# RF-Test-1.net
KiCad netlist of a schematic drawn in EAGLE
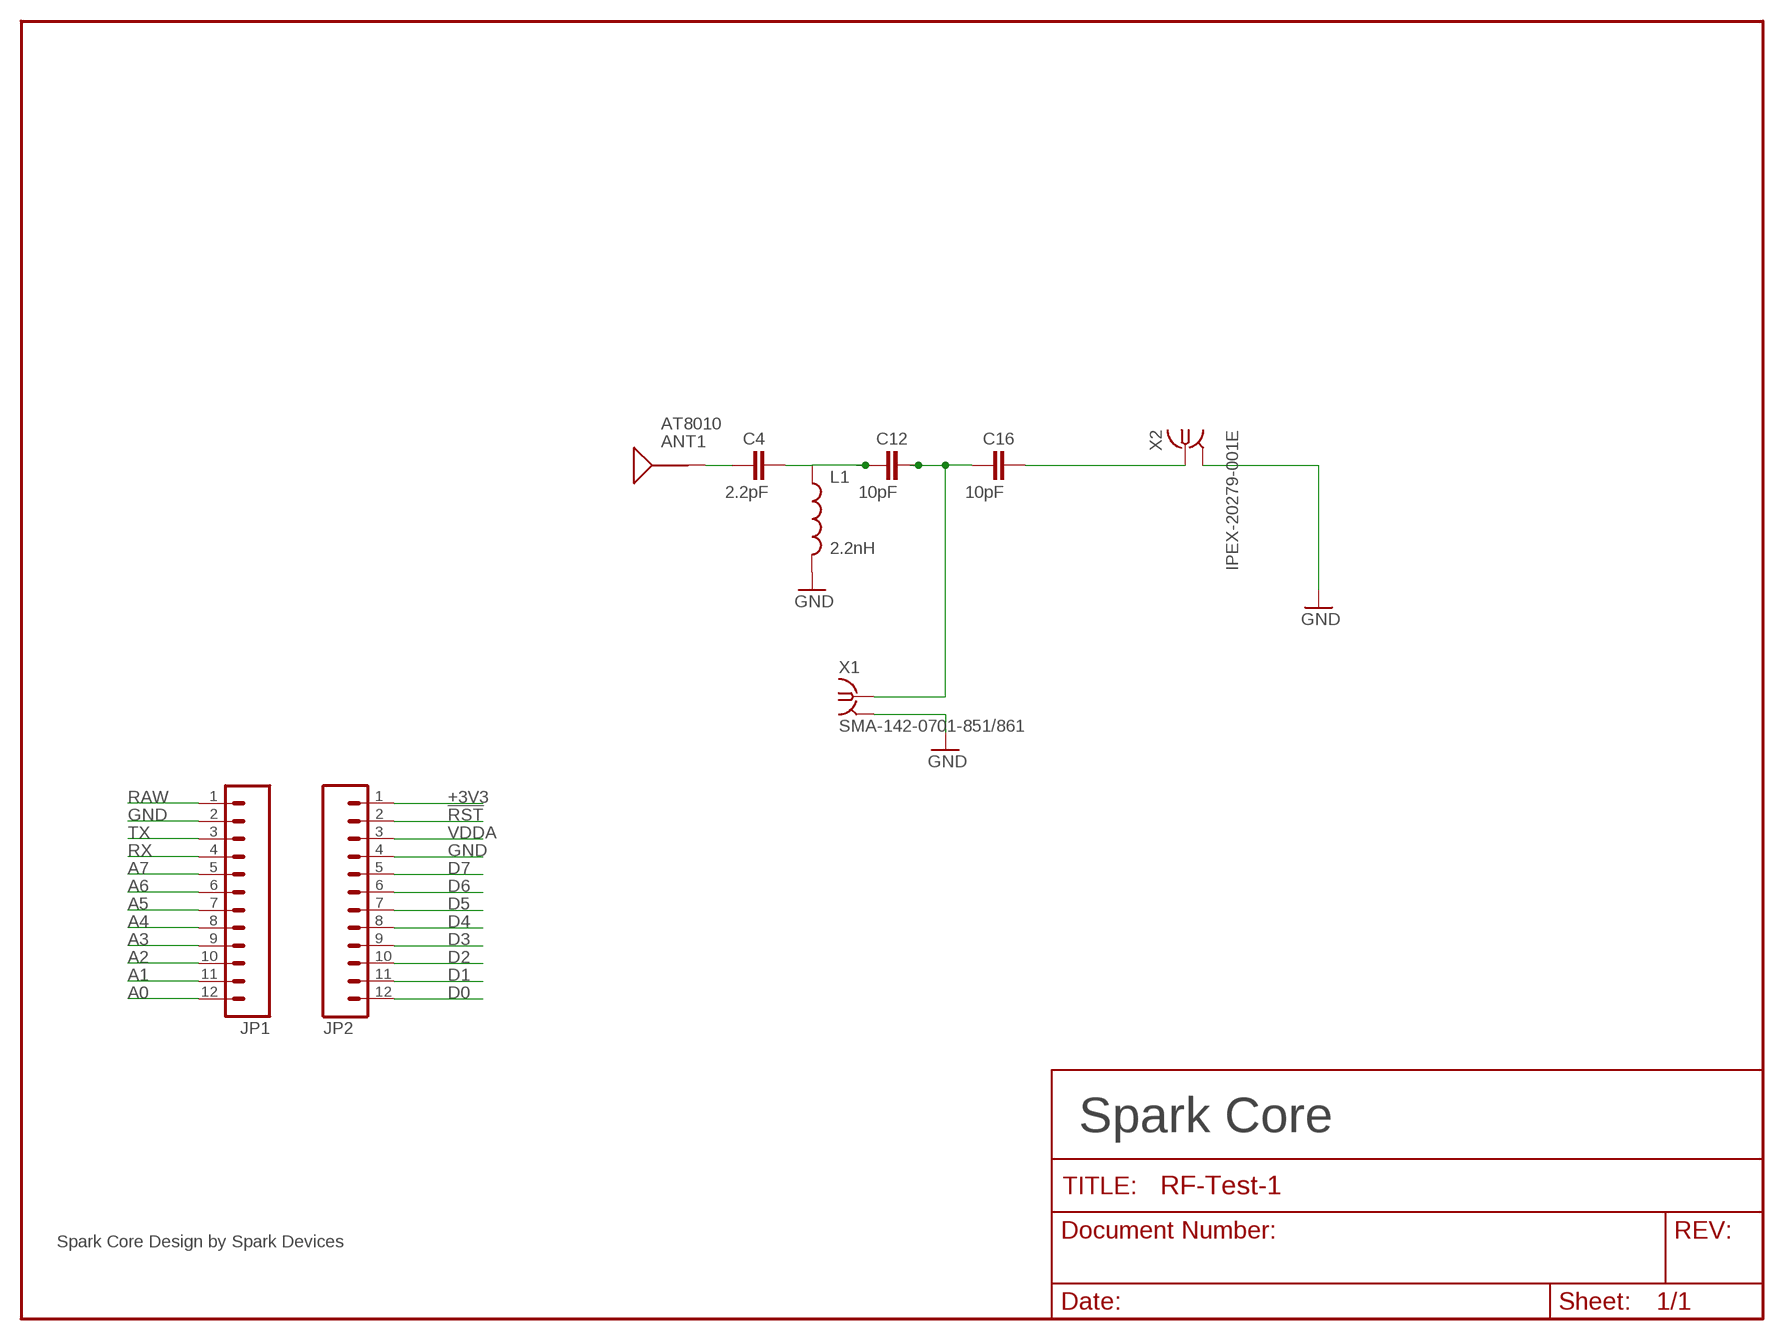
[diagram p0: schematic, sheet 1]

(export (version "E")
  (design (tool "Eeschema 10.0.6"))
  (components
    (comp (ref "ANT1")
      (value "AT8010")
      (footprint "eagle-import:AT8010")
      (libsource (lib "eagle-import") (part "AT8010"))
    )
    (comp (ref "C4")
      (value "2.2pF")
      (footprint "eagle-import:C0603")
      (libsource (lib "eagle-import") (part "C-EUC0603"))
    )
    (comp (ref "C12")
      (value "10pF")
      (footprint "eagle-import:C0603")
      (libsource (lib "eagle-import") (part "C-EUC0603"))
    )
    (comp (ref "C16")
      (value "10pF")
      (footprint "eagle-import:C0603")
      (libsource (lib "eagle-import") (part "C-EUC0603"))
    )
    (comp (ref "JP1")
      (value "M12PTH")
      (footprint "eagle-import:1X12")
      (libsource (lib "eagle-import") (part "M12PTH"))
    )
    (comp (ref "JP2")
      (value "M12PTH")
      (footprint "eagle-import:1X12")
      (libsource (lib "eagle-import") (part "M12PTH"))
    )
    (comp (ref "L1")
      (value "2.2nH")
      (footprint "eagle-import:0603")
      (libsource (lib "eagle-import") (part "INDUCTOR0603"))
    )
    (comp (ref "X1")
      (value "SMA-142-0701-851/861")
      (footprint "eagle-import:J502-ND-142-0701-851_861")
      (fields (field (name "MF") "JOHNSON COMPONENTS") (field (name "MPN") "142-0701-851"))
      (libsource (lib "eagle-import") (part "SMA-142-0701-851/861"))
    )
    (comp (ref "X2")
      (value "IPEX-20279-001E")
      (footprint "eagle-import:IPEX-20279-001E")
      (libsource (lib "eagle-import") (part "IPEX-20279-001E"))
    )
  )
  (nets
    (net (code "1") (name "/+3V3") (class "Default")
      (node (ref "JP2") (pin "1") (pinfunction "1_1") (pintype "passive"))
    )
    (net (code "2") (name "/A0") (class "Default")
      (node (ref "JP1") (pin "12") (pinfunction "12_12") (pintype "passive"))
    )
    (net (code "3") (name "/A1") (class "Default")
      (node (ref "JP1") (pin "11") (pinfunction "11_11") (pintype "passive"))
    )
    (net (code "4") (name "/A2") (class "Default")
      (node (ref "JP1") (pin "10") (pinfunction "10_10") (pintype "passive"))
    )
    (net (code "5") (name "/A3") (class "Default")
      (node (ref "JP1") (pin "9") (pinfunction "9_9") (pintype "passive"))
    )
    (net (code "6") (name "/A4") (class "Default")
      (node (ref "JP1") (pin "8") (pinfunction "8_8") (pintype "passive"))
    )
    (net (code "7") (name "/A5") (class "Default")
      (node (ref "JP1") (pin "7") (pinfunction "7_7") (pintype "passive"))
    )
    (net (code "8") (name "/A6") (class "Default")
      (node (ref "JP1") (pin "6") (pinfunction "6_6") (pintype "passive"))
    )
    (net (code "9") (name "/A7") (class "Default")
      (node (ref "JP1") (pin "5") (pinfunction "5_5") (pintype "passive"))
    )
    (net (code "10") (name "/D0") (class "Default")
      (node (ref "JP2") (pin "12") (pinfunction "12_12") (pintype "passive"))
    )
    (net (code "11") (name "/D1") (class "Default")
      (node (ref "JP2") (pin "11") (pinfunction "11_11") (pintype "passive"))
    )
    (net (code "12") (name "/D2") (class "Default")
      (node (ref "JP2") (pin "10") (pinfunction "10_10") (pintype "passive"))
    )
    (net (code "13") (name "/D3") (class "Default")
      (node (ref "JP2") (pin "9") (pinfunction "9_9") (pintype "passive"))
    )
    (net (code "14") (name "/D4") (class "Default")
      (node (ref "JP2") (pin "8") (pinfunction "8_8") (pintype "passive"))
    )
    (net (code "15") (name "/D5") (class "Default")
      (node (ref "JP2") (pin "7") (pinfunction "7_7") (pintype "passive"))
    )
    (net (code "16") (name "/D6") (class "Default")
      (node (ref "JP2") (pin "6") (pinfunction "6_6") (pintype "passive"))
    )
    (net (code "17") (name "/D7") (class "Default")
      (node (ref "JP2") (pin "5") (pinfunction "5_5") (pintype "passive"))
    )
    (net (code "18") (name "/RAW") (class "Default")
      (node (ref "JP1") (pin "1") (pinfunction "1_1") (pintype "passive"))
    )
    (net (code "19") (name "/RX") (class "Default")
      (node (ref "JP1") (pin "4") (pinfunction "4_4") (pintype "passive"))
    )
    (net (code "20") (name "/TX") (class "Default")
      (node (ref "JP1") (pin "3") (pinfunction "3_3") (pintype "passive"))
    )
    (net (code "21") (name "/VDDA") (class "Default")
      (node (ref "JP2") (pin "3") (pinfunction "3_3") (pintype "passive"))
    )
    (net (code "22") (name "/~{RST}") (class "Default")
      (node (ref "JP2") (pin "2") (pinfunction "2_2") (pintype "passive"))
    )
    (net (code "23") (name "GND") (class "Default")
      (node (ref "JP1") (pin "2") (pinfunction "2_2") (pintype "passive"))
      (node (ref "JP2") (pin "4") (pinfunction "4_4") (pintype "passive"))
      (node (ref "L1") (pin "2") (pinfunction "2_2") (pintype "passive"))
      (node (ref "X1") (pin "G@1") (pinfunction "2_G@1") (pintype "passive"))
      (node (ref "X1") (pin "G@2") (pinfunction "2_G@2") (pintype "passive"))
      (node (ref "X1") (pin "G@3") (pinfunction "2_G@3") (pintype "passive"))
      (node (ref "X1") (pin "G@4") (pinfunction "2_G@4") (pintype "passive"))
      (node (ref "X2") (pin "2@1") (pinfunction "GND_2@1") (pintype "passive"))
      (node (ref "X2") (pin "2@2") (pinfunction "GND_2@2") (pintype "passive"))
    )
    (net (code "24") (name "Net-(ANT1-SIGNAL)") (class "Default")
      (node (ref "ANT1") (pin "SIG") (pinfunction "SIGNAL_SIG") (pintype "bidirectional"))
      (node (ref "C4") (pin "1") (pinfunction "1_1") (pintype "passive"))
    )
    (net (code "25") (name "Net-(C12-Pad1)") (class "Default")
      (node (ref "C12") (pin "1") (pinfunction "1_1") (pintype "passive"))
      (node (ref "C4") (pin "2") (pinfunction "2_2") (pintype "passive"))
      (node (ref "L1") (pin "1") (pinfunction "1_1") (pintype "passive"))
    )
    (net (code "26") (name "Net-(C12-Pad2)") (class "Default")
      (node (ref "C12") (pin "2") (pinfunction "2_2") (pintype "passive"))
      (node (ref "C16") (pin "1") (pinfunction "1_1") (pintype "passive"))
      (node (ref "X1") (pin "1") (pinfunction "1_1") (pintype "passive"))
    )
    (net (code "27") (name "Net-(C16-Pad2)") (class "Default")
      (node (ref "C16") (pin "2") (pinfunction "2_2") (pintype "passive"))
      (node (ref "X2") (pin "1") (pinfunction "1_1") (pintype "passive"))
    )
  )
)
